# schematic.net
KiCad netlist of a schematic drawn in EAGLE
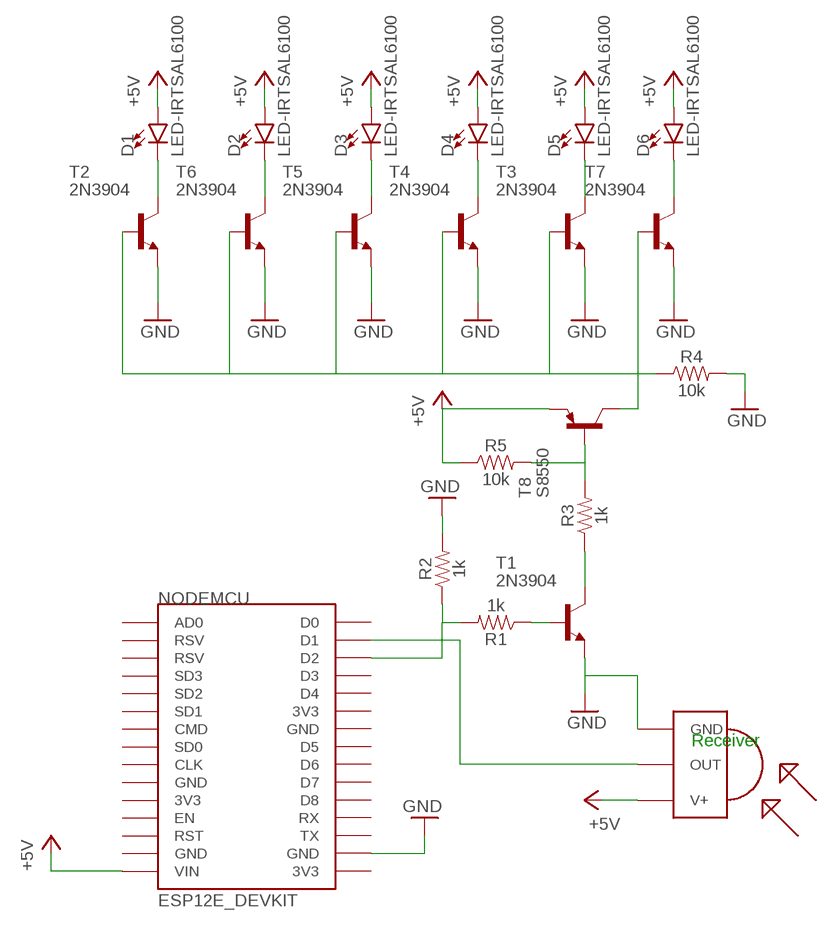
[diagram p0: schematic, sheet 1]

(export (version "E")
  (design (tool "Eeschema 10.0.6"))
  (components
    (comp (ref "D1")
      (value "LED-IRTSAL6100")
      (footprint "eagle-import:LED_5MM")
      (libsource (lib "eagle-import") (part "LED-IRTSAL6100"))
    )
    (comp (ref "D2")
      (value "LED-IRTSAL6100")
      (footprint "eagle-import:LED_5MM")
      (libsource (lib "eagle-import") (part "LED-IRTSAL6100"))
    )
    (comp (ref "D3")
      (value "LED-IRTSAL6100")
      (footprint "eagle-import:LED_5MM")
      (libsource (lib "eagle-import") (part "LED-IRTSAL6100"))
    )
    (comp (ref "D4")
      (value "LED-IRTSAL6100")
      (footprint "eagle-import:LED_5MM")
      (libsource (lib "eagle-import") (part "LED-IRTSAL6100"))
    )
    (comp (ref "D5")
      (value "LED-IRTSAL6100")
      (footprint "eagle-import:LED_5MM")
      (libsource (lib "eagle-import") (part "LED-IRTSAL6100"))
    )
    (comp (ref "D6")
      (value "LED-IRTSAL6100")
      (footprint "eagle-import:LED_5MM")
      (libsource (lib "eagle-import") (part "LED-IRTSAL6100"))
    )
    (comp (ref "NODEMCU")
      (value "ESP12E_DEVKIT")
      (footprint "eagle-import:ESP12E_DEVKIT")
      (libsource (lib "eagle-import") (part "ESP12E_DEVKIT"))
    )
    (comp (ref "R1")
      (value "1k")
      (footprint "eagle-import:AXIAL-0.3")
      (fields (field (name "MF") "FARNELL") (field (name "MPN") "MCF 0.25W 1K"))
      (libsource (lib "eagle-import") (part "1KOHM-HORIZ-1/4W-1%"))
    )
    (comp (ref "R2")
      (value "1k")
      (footprint "eagle-import:AXIAL-0.3")
      (fields (field (name "MF") "FARNELL") (field (name "MPN") "MCF 0.25W 1K"))
      (libsource (lib "eagle-import") (part "1KOHM-HORIZ-1/4W-1%"))
    )
    (comp (ref "R3")
      (value "1k")
      (footprint "eagle-import:AXIAL-0.3")
      (fields (field (name "MF") "FARNELL") (field (name "MPN") "MCF 0.25W 1K"))
      (libsource (lib "eagle-import") (part "1KOHM-HORIZ-1/4W-1%"))
    )
    (comp (ref "R4")
      (value "10k")
      (footprint "eagle-import:AXIAL-0.3")
      (fields (field (name "MF") "FARNELL") (field (name "MPN") "MCF 0.25W 10K"))
      (libsource (lib "eagle-import") (part "10KOHM-HORIZ-1/4W-1%"))
    )
    (comp (ref "R5")
      (value "10k")
      (footprint "eagle-import:AXIAL-0.3")
      (fields (field (name "MF") "FARNELL") (field (name "MPN") "MCF 0.25W 10K"))
      (libsource (lib "eagle-import") (part "10KOHM-HORIZ-1/4W-1%"))
    )
    (comp (ref "RECEIVER")
      (value "TSOP4838")
      (footprint "eagle-import:TSOP18XX")
      (fields (field (name "MF") "VISHAY/TELEFUNKEN"))
      (libsource (lib "eagle-import") (part "TSOP4838"))
    )
    (comp (ref "T1")
      (value "2N3904")
      (footprint "eagle-import:TO92")
      (fields (field (name "MF") "FAIRCHILD SEMICONDUCTOR") (field (name "MPN") "2N3904BU"))
      (libsource (lib "eagle-import") (part "2N3904"))
    )
    (comp (ref "T2")
      (value "2N3904")
      (footprint "eagle-import:TO92")
      (fields (field (name "MF") "FAIRCHILD SEMICONDUCTOR") (field (name "MPN") "2N3904BU"))
      (libsource (lib "eagle-import") (part "2N3904"))
    )
    (comp (ref "T3")
      (value "2N3904")
      (footprint "eagle-import:TO92")
      (fields (field (name "MF") "FAIRCHILD SEMICONDUCTOR") (field (name "MPN") "2N3904BU"))
      (libsource (lib "eagle-import") (part "2N3904"))
    )
    (comp (ref "T4")
      (value "2N3904")
      (footprint "eagle-import:TO92")
      (fields (field (name "MF") "FAIRCHILD SEMICONDUCTOR") (field (name "MPN") "2N3904BU"))
      (libsource (lib "eagle-import") (part "2N3904"))
    )
    (comp (ref "T5")
      (value "2N3904")
      (footprint "eagle-import:TO92")
      (fields (field (name "MF") "FAIRCHILD SEMICONDUCTOR") (field (name "MPN") "2N3904BU"))
      (libsource (lib "eagle-import") (part "2N3904"))
    )
    (comp (ref "T6")
      (value "2N3904")
      (footprint "eagle-import:TO92")
      (fields (field (name "MF") "FAIRCHILD SEMICONDUCTOR") (field (name "MPN") "2N3904BU"))
      (libsource (lib "eagle-import") (part "2N3904"))
    )
    (comp (ref "T7")
      (value "2N3904")
      (footprint "eagle-import:TO92")
      (fields (field (name "MF") "FAIRCHILD SEMICONDUCTOR") (field (name "MPN") "2N3904BU"))
      (libsource (lib "eagle-import") (part "2N3904"))
    )
    (comp (ref "T8")
      (value "S8550")
      (footprint "eagle-import:TO92-EBC")
      (libsource (lib "eagle-import") (part "-PNP-TO92-EBC"))
    )
  )
  (nets
    (net (code "1") (name "+5V") (class "Default")
      (node (ref "D1") (pin "A") (pinfunction "A_A") (pintype "passive"))
      (node (ref "D2") (pin "A") (pinfunction "A_A") (pintype "passive"))
      (node (ref "D3") (pin "A") (pinfunction "A_A") (pintype "passive"))
      (node (ref "D4") (pin "A") (pinfunction "A_A") (pintype "passive"))
      (node (ref "D5") (pin "A") (pinfunction "A_A") (pintype "passive"))
      (node (ref "D6") (pin "A") (pinfunction "A_A") (pintype "passive"))
      (node (ref "NODEMCU") (pin "VIN") (pinfunction "VIN_VIN") (pintype "bidirectional"))
      (node (ref "R5") (pin "P$1") (pinfunction "1_P$1") (pintype "passive"))
      (node (ref "RECEIVER") (pin "VCC") (pinfunction "V+_VCC") (pintype "bidirectional"))
      (node (ref "T8") (pin "E") (pinfunction "E_E") (pintype "passive"))
    )
    (net (code "2") (name "GND") (class "Default")
      (node (ref "NODEMCU") (pin "GND@3") (pinfunction "GND_GND@3") (pintype "bidirectional"))
      (node (ref "R2") (pin "P$2") (pinfunction "2_P$2") (pintype "passive"))
      (node (ref "R4") (pin "P$2") (pinfunction "2_P$2") (pintype "passive"))
      (node (ref "RECEIVER") (pin "GND") (pinfunction "GND_GND") (pintype "bidirectional"))
      (node (ref "T1") (pin "3") (pinfunction "E_3") (pintype "passive"))
      (node (ref "T2") (pin "3") (pinfunction "E_3") (pintype "passive"))
      (node (ref "T3") (pin "3") (pinfunction "E_3") (pintype "passive"))
      (node (ref "T4") (pin "3") (pinfunction "E_3") (pintype "passive"))
      (node (ref "T5") (pin "3") (pinfunction "E_3") (pintype "passive"))
      (node (ref "T6") (pin "3") (pinfunction "E_3") (pintype "passive"))
      (node (ref "T7") (pin "3") (pinfunction "E_3") (pintype "passive"))
    )
    (net (code "3") (name "Net-(D1-C)") (class "Default")
      (node (ref "D1") (pin "K") (pinfunction "C_K") (pintype "passive"))
      (node (ref "T2") (pin "1") (pinfunction "C_1") (pintype "passive"))
    )
    (net (code "4") (name "Net-(D2-C)") (class "Default")
      (node (ref "D2") (pin "K") (pinfunction "C_K") (pintype "passive"))
      (node (ref "T6") (pin "1") (pinfunction "C_1") (pintype "passive"))
    )
    (net (code "5") (name "Net-(D3-C)") (class "Default")
      (node (ref "D3") (pin "K") (pinfunction "C_K") (pintype "passive"))
      (node (ref "T5") (pin "1") (pinfunction "C_1") (pintype "passive"))
    )
    (net (code "6") (name "Net-(D4-C)") (class "Default")
      (node (ref "D4") (pin "K") (pinfunction "C_K") (pintype "passive"))
      (node (ref "T4") (pin "1") (pinfunction "C_1") (pintype "passive"))
    )
    (net (code "7") (name "Net-(D5-C)") (class "Default")
      (node (ref "D5") (pin "K") (pinfunction "C_K") (pintype "passive"))
      (node (ref "T3") (pin "1") (pinfunction "C_1") (pintype "passive"))
    )
    (net (code "8") (name "Net-(D6-C)") (class "Default")
      (node (ref "D6") (pin "K") (pinfunction "C_K") (pintype "passive"))
      (node (ref "T7") (pin "1") (pinfunction "C_1") (pintype "passive"))
    )
    (net (code "9") (name "Net-(NODEMCU-PadD1)") (class "Default")
      (node (ref "NODEMCU") (pin "D1") (pinfunction "D1_D1") (pintype "bidirectional"))
      (node (ref "RECEIVER") (pin "OUT") (pinfunction "OUT_OUT") (pintype "bidirectional"))
    )
    (net (code "10") (name "Net-(R1-1)") (class "Default")
      (node (ref "R1") (pin "P$1") (pinfunction "1_P$1") (pintype "passive"))
      (node (ref "T1") (pin "2") (pinfunction "B_2") (pintype "passive"))
    )
    (net (code "11") (name "Net-(R1-2)") (class "Default")
      (node (ref "NODEMCU") (pin "D2") (pinfunction "D2_D2") (pintype "bidirectional"))
      (node (ref "R1") (pin "P$2") (pinfunction "2_P$2") (pintype "passive"))
      (node (ref "R2") (pin "P$1") (pinfunction "1_P$1") (pintype "passive"))
    )
    (net (code "12") (name "Net-(R3-1)") (class "Default")
      (node (ref "R3") (pin "P$1") (pinfunction "1_P$1") (pintype "passive"))
      (node (ref "T1") (pin "1") (pinfunction "C_1") (pintype "passive"))
    )
    (net (code "13") (name "Net-(R3-2)") (class "Default")
      (node (ref "R3") (pin "P$2") (pinfunction "2_P$2") (pintype "passive"))
      (node (ref "R5") (pin "P$2") (pinfunction "2_P$2") (pintype "passive"))
      (node (ref "T8") (pin "B") (pinfunction "B_B") (pintype "passive"))
    )
    (net (code "14") (name "Net-(R4-1)") (class "Default")
      (node (ref "R4") (pin "P$1") (pinfunction "1_P$1") (pintype "passive"))
      (node (ref "T2") (pin "2") (pinfunction "B_2") (pintype "passive"))
      (node (ref "T3") (pin "2") (pinfunction "B_2") (pintype "passive"))
      (node (ref "T4") (pin "2") (pinfunction "B_2") (pintype "passive"))
      (node (ref "T5") (pin "2") (pinfunction "B_2") (pintype "passive"))
      (node (ref "T6") (pin "2") (pinfunction "B_2") (pintype "passive"))
      (node (ref "T7") (pin "2") (pinfunction "B_2") (pintype "passive"))
      (node (ref "T8") (pin "C") (pinfunction "C_C") (pintype "passive"))
    )
    (net (code "15") (name "unconnected-(NODEMCU-3V3-Pad3V3@0)") (class "Default")
      (node (ref "NODEMCU") (pin "3V3@0") (pinfunction "3V3_3V3@0") (pintype "bidirectional"))
    )
    (net (code "16") (name "unconnected-(NODEMCU-3V3-Pad3V3@1)") (class "Default")
      (node (ref "NODEMCU") (pin "3V3@1") (pinfunction "3V3_3V3@1") (pintype "bidirectional"))
    )
    (net (code "17") (name "unconnected-(NODEMCU-3V3-Pad3V3@2)") (class "Default")
      (node (ref "NODEMCU") (pin "3V3@2") (pinfunction "3V3_3V3@2") (pintype "bidirectional"))
    )
    (net (code "18") (name "unconnected-(NODEMCU-GND-PadGND@0)") (class "Default")
      (node (ref "NODEMCU") (pin "GND@0") (pinfunction "GND_GND@0") (pintype "bidirectional"))
    )
    (net (code "19") (name "unconnected-(NODEMCU-GND-PadGND@1)") (class "Default")
      (node (ref "NODEMCU") (pin "GND@1") (pinfunction "GND_GND@1") (pintype "bidirectional"))
    )
    (net (code "20") (name "unconnected-(NODEMCU-GND-PadGND@2)") (class "Default")
      (node (ref "NODEMCU") (pin "GND@2") (pinfunction "GND_GND@2") (pintype "bidirectional"))
    )
    (net (code "21") (name "unconnected-(NODEMCU-PadAD0)") (class "Default")
      (node (ref "NODEMCU") (pin "AD0") (pinfunction "AD0_AD0") (pintype "bidirectional"))
    )
    (net (code "22") (name "unconnected-(NODEMCU-PadCLK)") (class "Default")
      (node (ref "NODEMCU") (pin "CLK") (pinfunction "CLK_CLK") (pintype "bidirectional"))
    )
    (net (code "23") (name "unconnected-(NODEMCU-PadCMD)") (class "Default")
      (node (ref "NODEMCU") (pin "CMD") (pinfunction "CMD_CMD") (pintype "bidirectional"))
    )
    (net (code "24") (name "unconnected-(NODEMCU-PadD0)") (class "Default")
      (node (ref "NODEMCU") (pin "D0") (pinfunction "D0_D0") (pintype "bidirectional"))
    )
    (net (code "25") (name "unconnected-(NODEMCU-PadD3)") (class "Default")
      (node (ref "NODEMCU") (pin "D3") (pinfunction "D3_D3") (pintype "bidirectional"))
    )
    (net (code "26") (name "unconnected-(NODEMCU-PadD4)") (class "Default")
      (node (ref "NODEMCU") (pin "D4") (pinfunction "D4_D4") (pintype "bidirectional"))
    )
    (net (code "27") (name "unconnected-(NODEMCU-PadD5)") (class "Default")
      (node (ref "NODEMCU") (pin "D5") (pinfunction "D5_D5") (pintype "bidirectional"))
    )
    (net (code "28") (name "unconnected-(NODEMCU-PadD6)") (class "Default")
      (node (ref "NODEMCU") (pin "D6") (pinfunction "D6_D6") (pintype "bidirectional"))
    )
    (net (code "29") (name "unconnected-(NODEMCU-PadD7)") (class "Default")
      (node (ref "NODEMCU") (pin "D7") (pinfunction "D7_D7") (pintype "bidirectional"))
    )
    (net (code "30") (name "unconnected-(NODEMCU-PadD8)") (class "Default")
      (node (ref "NODEMCU") (pin "D8") (pinfunction "D8_D8") (pintype "bidirectional"))
    )
    (net (code "31") (name "unconnected-(NODEMCU-PadEN)") (class "Default")
      (node (ref "NODEMCU") (pin "EN") (pinfunction "EN_EN") (pintype "bidirectional"))
    )
    (net (code "32") (name "unconnected-(NODEMCU-PadRST)") (class "Default")
      (node (ref "NODEMCU") (pin "RST") (pinfunction "RST_RST") (pintype "bidirectional"))
    )
    (net (code "33") (name "unconnected-(NODEMCU-PadRX)") (class "Default")
      (node (ref "NODEMCU") (pin "RX") (pinfunction "RX_RX") (pintype "bidirectional"))
    )
    (net (code "34") (name "unconnected-(NODEMCU-PadSD0)") (class "Default")
      (node (ref "NODEMCU") (pin "SD0") (pinfunction "SD0_SD0") (pintype "bidirectional"))
    )
    (net (code "35") (name "unconnected-(NODEMCU-PadSD1)") (class "Default")
      (node (ref "NODEMCU") (pin "SD1") (pinfunction "SD1_SD1") (pintype "bidirectional"))
    )
    (net (code "36") (name "unconnected-(NODEMCU-PadSD2)") (class "Default")
      (node (ref "NODEMCU") (pin "SD2") (pinfunction "SD2_SD2") (pintype "bidirectional"))
    )
    (net (code "37") (name "unconnected-(NODEMCU-PadSD3)") (class "Default")
      (node (ref "NODEMCU") (pin "SD3") (pinfunction "SD3_SD3") (pintype "bidirectional"))
    )
    (net (code "38") (name "unconnected-(NODEMCU-PadTX)") (class "Default")
      (node (ref "NODEMCU") (pin "TX") (pinfunction "TX_TX") (pintype "bidirectional"))
    )
    (net (code "39") (name "unconnected-(NODEMCU-RSV-PadRSV@0)") (class "Default")
      (node (ref "NODEMCU") (pin "RSV@0") (pinfunction "RSV_RSV@0") (pintype "bidirectional"))
    )
    (net (code "40") (name "unconnected-(NODEMCU-RSV-PadRSV@1)") (class "Default")
      (node (ref "NODEMCU") (pin "RSV@1") (pinfunction "RSV_RSV@1") (pintype "bidirectional"))
    )
  )
)
